# alhambra_ii_shield.net
KiCad netlist of a schematic drawn in Altium Designer
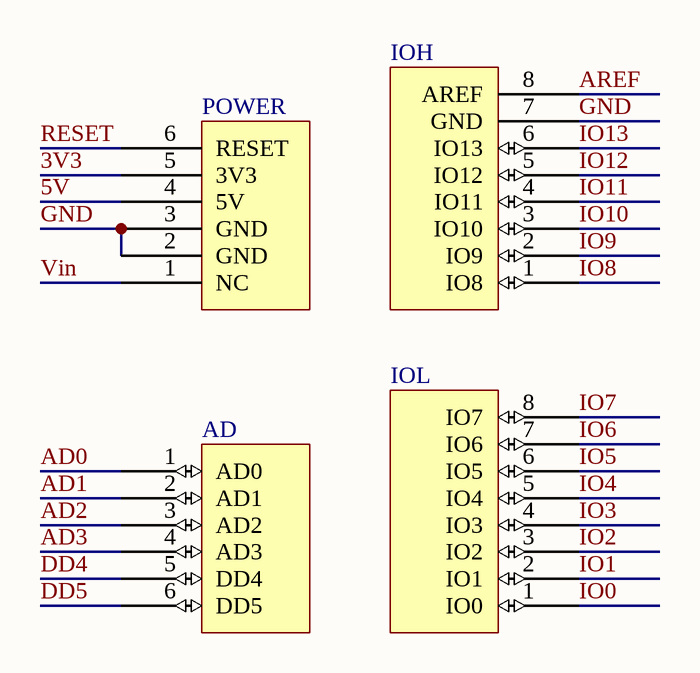
[diagram p0: alhambra_ii_shield.SchDoc]

(export (version "E")
  (design (tool "Eeschema 10.0.6"))
  (components
    (comp (ref "AD")
      (value "AD")
      (footprint "Header:Header 6x1 8.5mm")
      (libsource (lib "Header") (part "AD"))
    )
    (comp (ref "IOH") (value "IOH") (footprint "Header 8x1 8.5mm") (libsource (lib "Header") (part "IOH")))
    (comp (ref "IOL") (value "IOL") (footprint "Header 8x1 8.5mm") (libsource (lib "Header") (part "IOL")))
    (comp (ref "POWER")
      (value "POWER")
      (footprint "Header 6x1 8.5mm")
      (libsource (lib "Header") (part "POWER"))
    )
  )
  (nets
    (net (code "1") (name "/3V3") (class "Default")
      (node (ref "POWER") (pin "5") (pinfunction "3V3_5") (pintype "power_in"))
    )
    (net (code "2") (name "/5V") (class "Default")
      (node (ref "POWER") (pin "4") (pinfunction "5V_4") (pintype "power_in"))
    )
    (net (code "3") (name "/AD0") (class "Default")
      (node (ref "AD") (pin "1") (pinfunction "AD0_1") (pintype "bidirectional"))
    )
    (net (code "4") (name "/AD1") (class "Default")
      (node (ref "AD") (pin "2") (pinfunction "AD1_2") (pintype "bidirectional"))
    )
    (net (code "5") (name "/AD2") (class "Default")
      (node (ref "AD") (pin "3") (pinfunction "AD2_3") (pintype "bidirectional"))
    )
    (net (code "6") (name "/AD3") (class "Default")
      (node (ref "AD") (pin "4") (pinfunction "AD3_4") (pintype "bidirectional"))
    )
    (net (code "7") (name "/AREF") (class "Default")
      (node (ref "IOH") (pin "8") (pinfunction "AREF_8") (pintype "passive"))
    )
    (net (code "8") (name "/DD4") (class "Default")
      (node (ref "AD") (pin "5") (pinfunction "DD4_5") (pintype "bidirectional"))
    )
    (net (code "9") (name "/DD5") (class "Default")
      (node (ref "AD") (pin "6") (pinfunction "DD5_6") (pintype "bidirectional"))
    )
    (net (code "10") (name "/GND") (class "Default")
      (node (ref "IOH") (pin "7") (pinfunction "GND_7") (pintype "power_in"))
      (node (ref "POWER") (pin "2") (pinfunction "GND_2") (pintype "power_in"))
      (node (ref "POWER") (pin "3") (pinfunction "GND_3") (pintype "power_in"))
    )
    (net (code "11") (name "/IO0") (class "Default")
      (node (ref "IOL") (pin "1") (pinfunction "IO0_1") (pintype "bidirectional"))
    )
    (net (code "12") (name "/IO1") (class "Default")
      (node (ref "IOL") (pin "2") (pinfunction "IO1_2") (pintype "bidirectional"))
    )
    (net (code "13") (name "/IO2") (class "Default")
      (node (ref "IOL") (pin "3") (pinfunction "IO2_3") (pintype "bidirectional"))
    )
    (net (code "14") (name "/IO3") (class "Default")
      (node (ref "IOL") (pin "4") (pinfunction "IO3_4") (pintype "bidirectional"))
    )
    (net (code "15") (name "/IO4") (class "Default")
      (node (ref "IOL") (pin "5") (pinfunction "IO4_5") (pintype "bidirectional"))
    )
    (net (code "16") (name "/IO5") (class "Default")
      (node (ref "IOL") (pin "6") (pinfunction "IO5_6") (pintype "bidirectional"))
    )
    (net (code "17") (name "/IO6") (class "Default")
      (node (ref "IOL") (pin "7") (pinfunction "IO6_7") (pintype "bidirectional"))
    )
    (net (code "18") (name "/IO7") (class "Default")
      (node (ref "IOL") (pin "8") (pinfunction "IO7_8") (pintype "bidirectional"))
    )
    (net (code "19") (name "/IO8") (class "Default")
      (node (ref "IOH") (pin "1") (pinfunction "IO8_1") (pintype "bidirectional"))
    )
    (net (code "20") (name "/IO9") (class "Default")
      (node (ref "IOH") (pin "2") (pinfunction "IO9_2") (pintype "bidirectional"))
    )
    (net (code "21") (name "/IO10") (class "Default")
      (node (ref "IOH") (pin "3") (pinfunction "IO10_3") (pintype "bidirectional"))
    )
    (net (code "22") (name "/IO11") (class "Default")
      (node (ref "IOH") (pin "4") (pinfunction "IO11_4") (pintype "bidirectional"))
    )
    (net (code "23") (name "/IO12") (class "Default")
      (node (ref "IOH") (pin "5") (pinfunction "IO12_5") (pintype "bidirectional"))
    )
    (net (code "24") (name "/IO13") (class "Default")
      (node (ref "IOH") (pin "6") (pinfunction "IO13_6") (pintype "bidirectional"))
    )
    (net (code "25") (name "/RESET") (class "Default")
      (node (ref "POWER") (pin "6") (pinfunction "RESET_6") (pintype "passive"))
    )
    (net (code "26") (name "/Vin") (class "Default")
      (node (ref "POWER") (pin "1") (pinfunction "NC_1") (pintype "power_in"))
    )
  )
)
